# SensorThing_v1_0.net
KiCad netlist of a schematic drawn in Altium Designer
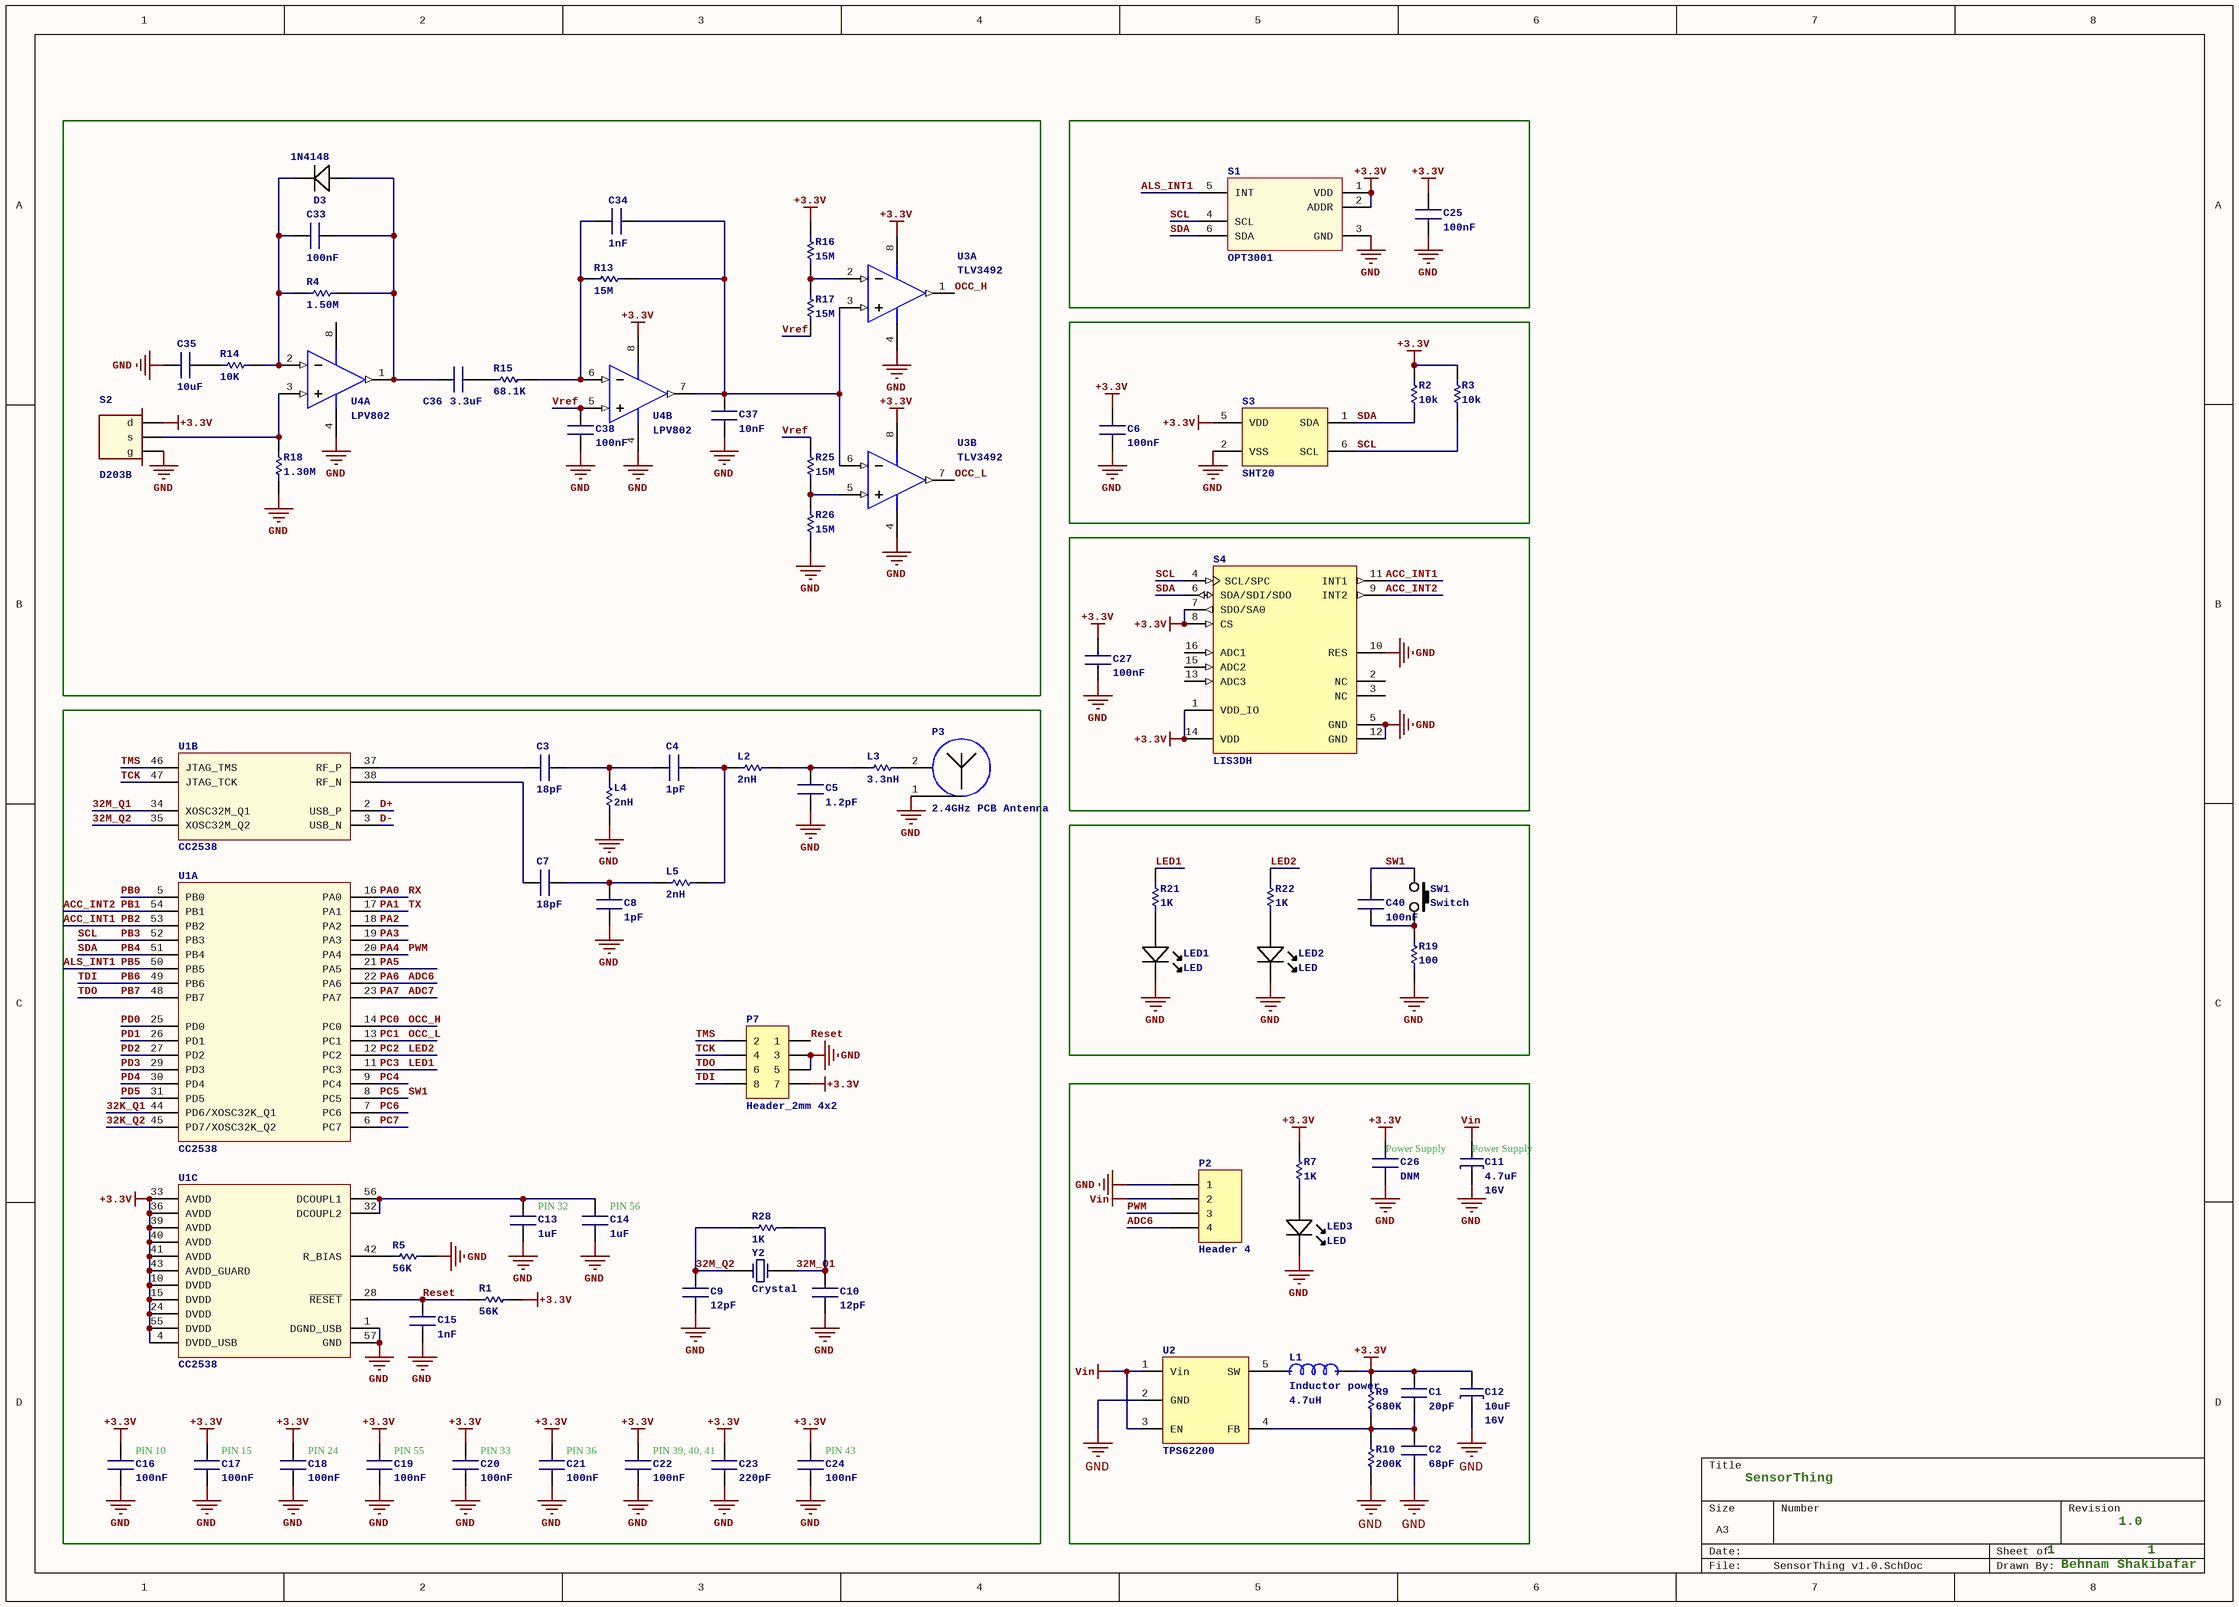
[diagram p0: SensorThing v1.0.SchDoc]

(export (version "E")
  (design (tool "Eeschema 10.0.6"))
  (components
    (comp (ref "C1")
      (value "Cap")
      (footprint "CAP 0603")
      (fields (field (name "VOLTAGE") "100V") (field (name "CAPACITY") "20pF"))
      (libsource (lib "Common") (part "Cap"))
    )
    (comp (ref "C2")
      (value "Cap")
      (footprint "CAP 0603")
      (fields (field (name "VOLTAGE") "100V") (field (name "CAPACITY") "68pF"))
      (libsource (lib "Common") (part "Cap"))
    )
    (comp (ref "C3")
      (value "Cap")
      (footprint "CAP 0603")
      (fields (field (name "VOLTAGE") "100V") (field (name "CAPACITY") "18pF"))
      (libsource (lib "Common") (part "Cap"))
    )
    (comp (ref "C4")
      (value "Cap")
      (footprint "CAP 0603")
      (fields (field (name "VOLTAGE") "100V") (field (name "CAPACITY") "1pF"))
      (libsource (lib "Common") (part "Cap"))
    )
    (comp (ref "C5")
      (value "Cap")
      (footprint "CAP 0603")
      (fields (field (name "VOLTAGE") "100V") (field (name "CAPACITY") "1.2pF"))
      (libsource (lib "Common") (part "Cap"))
    )
    (comp (ref "C6")
      (value "Cap")
      (footprint "CAP 0603")
      (fields (field (name "VOLTAGE") "100V") (field (name "CAPACITY") "100nF"))
      (libsource (lib "Common") (part "Cap"))
    )
    (comp (ref "C7")
      (value "Cap")
      (footprint "CAP 0603")
      (fields (field (name "VOLTAGE") "100V") (field (name "CAPACITY") "18pF"))
      (libsource (lib "Common") (part "Cap"))
    )
    (comp (ref "C8")
      (value "Cap")
      (footprint "CAP 0603")
      (fields (field (name "VOLTAGE") "100V") (field (name "CAPACITY") "1pF"))
      (libsource (lib "Common") (part "Cap"))
    )
    (comp (ref "C9")
      (value "Cap")
      (footprint "CAP 0603")
      (fields (field (name "VOLTAGE") "100V") (field (name "CAPACITY") "12pF"))
      (libsource (lib "Common") (part "Cap"))
    )
    (comp (ref "C10")
      (value "Cap")
      (footprint "CAP 0603")
      (fields (field (name "VOLTAGE") "100V") (field (name "CAPACITY") "12pF"))
      (libsource (lib "Common") (part "Cap"))
    )
    (comp (ref "C11")
      (value "Cap pol")
      (footprint "CAP A")
      (fields (field (name "CAPACITY") "4.7uF") (field (name "VOLTAGE") "16V"))
      (libsource (lib "Common") (part "Cap pol"))
    )
    (comp (ref "C12")
      (value "Cap pol")
      (footprint "CAP A")
      (fields (field (name "CAPACITY") "10uF") (field (name "VOLTAGE") "16V"))
      (libsource (lib "Common") (part "Cap pol"))
    )
    (comp (ref "C13")
      (value "Cap")
      (footprint "CAP 0603")
      (fields (field (name "VOLTAGE") "100V") (field (name "CAPACITY") "1uF"))
      (libsource (lib "Common") (part "Cap"))
    )
    (comp (ref "C14")
      (value "Cap")
      (footprint "CAP 0603")
      (fields (field (name "VOLTAGE") "100V") (field (name "CAPACITY") "1uF"))
      (libsource (lib "Common") (part "Cap"))
    )
    (comp (ref "C15")
      (value "Cap")
      (footprint "CAP 0603")
      (fields (field (name "VOLTAGE") "100V") (field (name "CAPACITY") "1nF"))
      (libsource (lib "Common") (part "Cap"))
    )
    (comp (ref "C16")
      (value "Cap")
      (footprint "CAP 0603")
      (fields (field (name "VOLTAGE") "100V") (field (name "CAPACITY") "100nF"))
      (libsource (lib "Common") (part "Cap"))
    )
    (comp (ref "C17")
      (value "Cap")
      (footprint "CAP 0603")
      (fields (field (name "VOLTAGE") "100V") (field (name "CAPACITY") "100nF"))
      (libsource (lib "Common") (part "Cap"))
    )
    (comp (ref "C18")
      (value "Cap")
      (footprint "CAP 0603")
      (fields (field (name "VOLTAGE") "100V") (field (name "CAPACITY") "100nF"))
      (libsource (lib "Common") (part "Cap"))
    )
    (comp (ref "C19")
      (value "Cap")
      (footprint "CAP 0603")
      (fields (field (name "VOLTAGE") "100V") (field (name "CAPACITY") "100nF"))
      (libsource (lib "Common") (part "Cap"))
    )
    (comp (ref "C20")
      (value "Cap")
      (footprint "CAP 0603")
      (fields (field (name "VOLTAGE") "100V") (field (name "CAPACITY") "100nF"))
      (libsource (lib "Common") (part "Cap"))
    )
    (comp (ref "C21")
      (value "Cap")
      (footprint "CAP 0603")
      (fields (field (name "VOLTAGE") "100V") (field (name "CAPACITY") "100nF"))
      (libsource (lib "Common") (part "Cap"))
    )
    (comp (ref "C22")
      (value "Cap")
      (footprint "CAP 0603")
      (fields (field (name "VOLTAGE") "100V") (field (name "CAPACITY") "100nF"))
      (libsource (lib "Common") (part "Cap"))
    )
    (comp (ref "C23")
      (value "Cap")
      (footprint "CAP 0603")
      (fields (field (name "VOLTAGE") "100V") (field (name "CAPACITY") "220pF"))
      (libsource (lib "Common") (part "Cap"))
    )
    (comp (ref "C24")
      (value "Cap")
      (footprint "CAP 0603")
      (fields (field (name "VOLTAGE") "100V") (field (name "CAPACITY") "100nF"))
      (libsource (lib "Common") (part "Cap"))
    )
    (comp (ref "C25")
      (value "Cap")
      (footprint "CAP 0603")
      (fields (field (name "VOLTAGE") "100V") (field (name "CAPACITY") "100nF"))
      (libsource (lib "Common") (part "Cap"))
    )
    (comp (ref "C26")
      (value "Cap")
      (footprint "CAP 0603")
      (fields (field (name "VOLTAGE") "100V") (field (name "CAPACITY") "DNM"))
      (libsource (lib "Common") (part "Cap"))
    )
    (comp (ref "C27")
      (value "Cap")
      (footprint "CAP 0603")
      (fields (field (name "VOLTAGE") "100V") (field (name "CAPACITY") "100nF"))
      (libsource (lib "Common") (part "Cap"))
    )
    (comp (ref "C33")
      (value "Cap")
      (footprint "CAP 0603")
      (fields (field (name "VOLTAGE") "100V") (field (name "CAPACITY") "100nF"))
      (libsource (lib "Common") (part "Cap"))
    )
    (comp (ref "C34")
      (value "Cap")
      (footprint "CAP 0603")
      (fields (field (name "VOLTAGE") "100V") (field (name "CAPACITY") "1nF"))
      (libsource (lib "Common") (part "Cap"))
    )
    (comp (ref "C35")
      (value "Cap")
      (footprint "CAP 0603")
      (fields (field (name "VOLTAGE") "100V") (field (name "CAPACITY") "10uF"))
      (libsource (lib "Common") (part "Cap"))
    )
    (comp (ref "C36")
      (value "Cap")
      (footprint "CAP 0603")
      (fields (field (name "VOLTAGE") "100V") (field (name "CAPACITY") "3.3uF"))
      (libsource (lib "Common") (part "Cap"))
    )
    (comp (ref "C37")
      (value "Cap")
      (footprint "CAP 0603")
      (fields (field (name "VOLTAGE") "100V") (field (name "CAPACITY") "10nF"))
      (libsource (lib "Common") (part "Cap"))
    )
    (comp (ref "C38")
      (value "Cap")
      (footprint "CAP 0603")
      (fields (field (name "VOLTAGE") "100V") (field (name "CAPACITY") "100nF"))
      (libsource (lib "Common") (part "Cap"))
    )
    (comp (ref "C40")
      (value "Cap")
      (footprint "CAP 0603")
      (fields (field (name "VOLTAGE") "100V") (field (name "CAPACITY") "100nF"))
      (libsource (lib "Common") (part "Cap"))
    )
    (comp (ref "D3") (value "1N4148") (footprint "SOD-523") (libsource (lib "Common") (part "Diode")))
    (comp (ref "L1")
      (value "Inductor power")
      (footprint "INDUCTOR 2520")
      (fields (field (name "ALTIUM_VALUE") "4.7uH"))
      (libsource (lib "Common") (part "Inductor power"))
    )
    (comp (ref "L2")
      (value "Res")
      (footprint "RES 0603")
      (description "Resistor")
      (fields (field (name "OHM") "2nH"))
      (libsource (lib "Common") (part "Res"))
    )
    (comp (ref "L3")
      (value "Res")
      (footprint "RES 0603")
      (description "Resistor")
      (fields (field (name "OHM") "3.3nH"))
      (libsource (lib "Common") (part "Res"))
    )
    (comp (ref "L4")
      (value "Res")
      (footprint "RES 0603")
      (description "Resistor")
      (fields (field (name "OHM") "2nH"))
      (libsource (lib "Common") (part "Res"))
    )
    (comp (ref "L5")
      (value "Res")
      (footprint "RES 0603")
      (description "Resistor")
      (fields (field (name "OHM") "2nH"))
      (libsource (lib "Common") (part "Res"))
    )
    (comp (ref "LED1")
      (value "LED")
      (footprint "LED 0603")
      (description "LED SMD")
      (libsource (lib "Common") (part "LED SMD"))
    )
    (comp (ref "LED2")
      (value "LED")
      (footprint "LED 0603")
      (description "LED SMD")
      (libsource (lib "Common") (part "LED SMD"))
    )
    (comp (ref "LED3")
      (value "LED")
      (footprint "LED 0603")
      (description "LED SMD")
      (libsource (lib "Common") (part "LED SMD"))
    )
    (comp (ref "P2")
      (value "Header 4")
      (footprint "HDR1X4")
      (description "Header, 4-Pin")
      (fields (field (name "PUBLISHER") "Altium Limited"))
      (libsource (lib "Miscellaneous Connectors") (part "Header 4"))
    )
    (comp (ref "P3")
      (value "2.4GHz PCB Antenna")
      (footprint "2.4 GHz Inverted F Antenna 1")
      (libsource (lib "My Lib") (part "2.4GHz PCB Antenna"))
    )
    (comp (ref "P7")
      (value "Header_2mm 4x2")
      (footprint "Header_2mm 4x2")
      (libsource (lib "Common") (part "Header_2mm 4x2"))
    )
    (comp (ref "R1")
      (value "Res")
      (footprint "RES 0603")
      (description "Resistor")
      (fields (field (name "OHM") "56K"))
      (libsource (lib "Common") (part "Res"))
    )
    (comp (ref "R2")
      (value "Res")
      (footprint "RES 0603")
      (description "Resistor")
      (fields (field (name "OHM") "10k"))
      (libsource (lib "Common") (part "Res"))
    )
    (comp (ref "R3")
      (value "Res")
      (footprint "RES 0603")
      (description "Resistor")
      (fields (field (name "OHM") "10k"))
      (libsource (lib "Common") (part "Res"))
    )
    (comp (ref "R4")
      (value "Res")
      (footprint "RES 0603")
      (description "Resistor")
      (fields (field (name "OHM") "1.50M"))
      (libsource (lib "Common") (part "Res"))
    )
    (comp (ref "R5")
      (value "Res")
      (footprint "RES 0603")
      (description "Resistor")
      (fields (field (name "OHM") "56K"))
      (libsource (lib "Common") (part "Res"))
    )
    (comp (ref "R7")
      (value "Res")
      (footprint "RES 0603")
      (description "Resistor")
      (fields (field (name "OHM") "1K"))
      (libsource (lib "Common") (part "Res"))
    )
    (comp (ref "R9")
      (value "Res")
      (footprint "RES 0603")
      (description "Resistor")
      (fields (field (name "OHM") "680K"))
      (libsource (lib "Common") (part "Res"))
    )
    (comp (ref "R10")
      (value "Res")
      (footprint "RES 0603")
      (description "Resistor")
      (fields (field (name "OHM") "200K"))
      (libsource (lib "Common") (part "Res"))
    )
    (comp (ref "R13")
      (value "Res")
      (footprint "RES 0603")
      (description "Resistor")
      (fields (field (name "OHM") "15M"))
      (libsource (lib "Common") (part "Res"))
    )
    (comp (ref "R14")
      (value "Res")
      (footprint "RES 0603")
      (description "Resistor")
      (fields (field (name "OHM") "10K"))
      (libsource (lib "Common") (part "Res"))
    )
    (comp (ref "R15")
      (value "Res")
      (footprint "RES 0603")
      (description "Resistor")
      (fields (field (name "OHM") "68.1K"))
      (libsource (lib "Common") (part "Res"))
    )
    (comp (ref "R16")
      (value "Res")
      (footprint "RES 0603")
      (description "Resistor")
      (fields (field (name "OHM") "15M"))
      (libsource (lib "Common") (part "Res"))
    )
    (comp (ref "R17")
      (value "Res")
      (footprint "RES 0603")
      (description "Resistor")
      (fields (field (name "OHM") "15M"))
      (libsource (lib "Common") (part "Res"))
    )
    (comp (ref "R18")
      (value "Res")
      (footprint "RES 0603")
      (description "Resistor")
      (fields (field (name "OHM") "1.30M"))
      (libsource (lib "Common") (part "Res"))
    )
    (comp (ref "R19")
      (value "Res")
      (footprint "RES 0603")
      (description "Resistor")
      (fields (field (name "OHM") "100"))
      (libsource (lib "Common") (part "Res"))
    )
    (comp (ref "R21")
      (value "Res")
      (footprint "RES 0603")
      (description "Resistor")
      (fields (field (name "OHM") "1K"))
      (libsource (lib "Common") (part "Res"))
    )
    (comp (ref "R22")
      (value "Res")
      (footprint "RES 0603")
      (description "Resistor")
      (fields (field (name "OHM") "1K"))
      (libsource (lib "Common") (part "Res"))
    )
    (comp (ref "R25")
      (value "Res")
      (footprint "RES 0603")
      (description "Resistor")
      (fields (field (name "OHM") "15M"))
      (libsource (lib "Common") (part "Res"))
    )
    (comp (ref "R26")
      (value "Res")
      (footprint "RES 0603")
      (description "Resistor")
      (fields (field (name "OHM") "15M"))
      (libsource (lib "Common") (part "Res"))
    )
    (comp (ref "R28")
      (value "Res")
      (footprint "RES 0603")
      (description "Resistor")
      (fields (field (name "OHM") "1K"))
      (libsource (lib "Common") (part "Res"))
    )
    (comp (ref "S1") (value "OPT3001") (footprint "USON-6pin") (libsource (lib "Chips") (part "OPT3001")))
    (comp (ref "S2") (value "D203B") (footprint "D203B") (libsource (lib "Common") (part "D203B PIR sensor")))
    (comp (ref "S3") (value "SHT20") (footprint "SHT20") (libsource (lib "My Lib") (part "SHT20")))
    (comp (ref "S4")
      (value "LIS3DH")
      (footprint "LGA16-3X3X1_N")
      (fields (field (name "MANUFACTURER") "STMicroelectronics"))
      (libsource (lib "STMicroelectronics Sensors & MEMS") (part "LIS3DH"))
    )
    (comp (ref "SW1")
      (value "Switch")
      (footprint "Switch Side-B3U")
      (description "micro Switch")
      (libsource (lib "Common") (part "Switch"))
    )
    (comp (ref "U1") (value "CC2538") (footprint "PVQFN56-CC2538") (libsource (lib "Chips") (part "CC2538")))
    (comp (ref "U2")
      (value "TPS62200")
      (footprint "SOT23-5")
      (description "NAND gate")
      (libsource (lib "My Lib") (part "TPS6220"))
    )
    (comp (ref "U3") (value "TLV3492") (footprint "VSSOP 8-Pin") (libsource (lib "My Lib") (part "TLV3492")))
    (comp (ref "U4") (value "LPV802") (footprint "VSSOP 8-Pin") (libsource (lib "My Lib") (part "LPV802")))
    (comp (ref "Y2") (value "Crystal") (footprint "Crystal 3225") (libsource (lib "Common") (part "Xtal")))
  )
  (nets
    (net (code "1") (name "+3.3V") (class "Default")
      (node (ref "C1") (pin "1") (pinfunction "1_1") (pintype "passive"))
      (node (ref "C12") (pin "1") (pinfunction "1_1") (pintype "passive"))
      (node (ref "C16") (pin "1") (pinfunction "1_1") (pintype "passive"))
      (node (ref "C17") (pin "1") (pinfunction "1_1") (pintype "passive"))
      (node (ref "C18") (pin "1") (pinfunction "1_1") (pintype "passive"))
      (node (ref "C19") (pin "1") (pinfunction "1_1") (pintype "passive"))
      (node (ref "C20") (pin "1") (pinfunction "1_1") (pintype "passive"))
      (node (ref "C21") (pin "1") (pinfunction "1_1") (pintype "passive"))
      (node (ref "C22") (pin "1") (pinfunction "1_1") (pintype "passive"))
      (node (ref "C23") (pin "1") (pinfunction "1_1") (pintype "passive"))
      (node (ref "C24") (pin "1") (pinfunction "1_1") (pintype "passive"))
      (node (ref "C25") (pin "1") (pinfunction "1_1") (pintype "passive"))
      (node (ref "C26") (pin "1") (pinfunction "1_1") (pintype "passive"))
      (node (ref "C27") (pin "1") (pinfunction "1_1") (pintype "passive"))
      (node (ref "C6") (pin "1") (pinfunction "1_1") (pintype "passive"))
      (node (ref "L1") (pin "2") (pinfunction "2_2") (pintype "passive"))
      (node (ref "P7") (pin "7") (pinfunction "7_7") (pintype "passive"))
      (node (ref "R1") (pin "2") (pinfunction "2_2") (pintype "passive"))
      (node (ref "R16") (pin "2") (pinfunction "2_2") (pintype "passive"))
      (node (ref "R2") (pin "1") (pinfunction "1_1") (pintype "passive"))
      (node (ref "R3") (pin "1") (pinfunction "1_1") (pintype "passive"))
      (node (ref "R7") (pin "1") (pinfunction "1_1") (pintype "passive"))
      (node (ref "R9") (pin "1") (pinfunction "1_1") (pintype "passive"))
      (node (ref "S1") (pin "1") (pinfunction "VDD_1") (pintype "power_in"))
      (node (ref "S1") (pin "2") (pinfunction "ADDR_2") (pintype "power_in"))
      (node (ref "S2") (pin "1") (pinfunction "d_1") (pintype "passive"))
      (node (ref "S3") (pin "5") (pinfunction "VDD_5") (pintype "passive"))
      (node (ref "S4") (pin "1") (pinfunction "VDD_IO_1") (pintype "power_in"))
      (node (ref "S4") (pin "14") (pinfunction "VDD_14") (pintype "power_in"))
      (node (ref "S4") (pin "7") (pinfunction "SDO/SA0_7") (pintype "output"))
      (node (ref "S4") (pin "8") (pinfunction "CS_8") (pintype "input"))
      (node (ref "U1") (pin "10") (pinfunction "DVDD_10") (pintype "power_in"))
      (node (ref "U1") (pin "15") (pinfunction "DVDD_15") (pintype "power_in"))
      (node (ref "U1") (pin "24") (pinfunction "DVDD_24") (pintype "power_in"))
      (node (ref "U1") (pin "33") (pinfunction "AVDD_33") (pintype "power_in"))
      (node (ref "U1") (pin "36") (pinfunction "AVDD_36") (pintype "power_in"))
      (node (ref "U1") (pin "39") (pinfunction "AVDD_39") (pintype "power_in"))
      (node (ref "U1") (pin "4") (pinfunction "DVDD_USB_4") (pintype "power_in"))
      (node (ref "U1") (pin "40") (pinfunction "AVDD_40") (pintype "power_in"))
      (node (ref "U1") (pin "41") (pinfunction "AVDD_41") (pintype "power_in"))
      (node (ref "U1") (pin "43") (pinfunction "AVDD_GUARD_43") (pintype "power_in"))
      (node (ref "U1") (pin "55") (pinfunction "DVDD_55") (pintype "power_in"))
      (node (ref "U3") (pin "8") (pinfunction "V+_8") (pintype "power_in"))
      (node (ref "U4") (pin "8") (pinfunction "V+_8") (pintype "power_in"))
    )
    (net (code "2") (name "/32K_Q1") (class "Default")
      (node (ref "U1") (pin "44") (pinfunction "PD6/XOSC32K_Q1_44") (pintype "power_in"))
    )
    (net (code "3") (name "/32K_Q2") (class "Default")
      (node (ref "U1") (pin "45") (pinfunction "PD7/XOSC32K_Q2_45") (pintype "power_in"))
    )
    (net (code "4") (name "/32M_Q1") (class "Default")
      (node (ref "C10") (pin "1") (pinfunction "1_1") (pintype "passive"))
      (node (ref "R28") (pin "2") (pinfunction "2_2") (pintype "passive"))
      (node (ref "U1") (pin "34") (pinfunction "XOSC32M_Q1_34") (pintype "passive"))
      (node (ref "Y2") (pin "2") (pinfunction "2_2") (pintype "passive"))
    )
    (net (code "5") (name "/32M_Q2") (class "Default")
      (node (ref "C9") (pin "1") (pinfunction "1_1") (pintype "passive"))
      (node (ref "R28") (pin "1") (pinfunction "1_1") (pintype "passive"))
      (node (ref "U1") (pin "35") (pinfunction "XOSC32M_Q2_35") (pintype "passive"))
      (node (ref "Y2") (pin "1") (pinfunction "1_1") (pintype "passive"))
    )
    (net (code "6") (name "/ACC_INT1") (class "Default")
      (node (ref "S4") (pin "11") (pinfunction "INT1_11") (pintype "output"))
      (node (ref "U1") (pin "53") (pinfunction "PB2_53") (pintype "power_in"))
    )
    (net (code "7") (name "/ACC_INT2") (class "Default")
      (node (ref "S4") (pin "9") (pinfunction "INT2_9") (pintype "output"))
      (node (ref "U1") (pin "54") (pinfunction "PB1_54") (pintype "power_in"))
    )
    (net (code "8") (name "/ADC6") (class "Default")
      (node (ref "P2") (pin "4") (pinfunction "4_4") (pintype "passive"))
      (node (ref "U1") (pin "22") (pinfunction "PA6_22") (pintype "power_in"))
    )
    (net (code "9") (name "/ADC7") (class "Default")
      (node (ref "U1") (pin "23") (pinfunction "PA7_23") (pintype "power_in"))
    )
    (net (code "10") (name "/ALS_INT1") (class "Default")
      (node (ref "S1") (pin "5") (pinfunction "INT_5") (pintype "power_in"))
      (node (ref "U1") (pin "50") (pinfunction "PB5_50") (pintype "power_in"))
    )
    (net (code "11") (name "/D+") (class "Default")
      (node (ref "U1") (pin "2") (pinfunction "USB_P_2") (pintype "passive"))
    )
    (net (code "12") (name "/D-") (class "Default")
      (node (ref "U1") (pin "3") (pinfunction "USB_N_3") (pintype "passive"))
    )
    (net (code "13") (name "/LED1") (class "Default")
      (node (ref "R21") (pin "1") (pinfunction "1_1") (pintype "passive"))
      (node (ref "U1") (pin "11") (pinfunction "PC3_11") (pintype "power_in"))
    )
    (net (code "14") (name "/LED2") (class "Default")
      (node (ref "R22") (pin "1") (pinfunction "1_1") (pintype "passive"))
      (node (ref "U1") (pin "12") (pinfunction "PC2_12") (pintype "power_in"))
    )
    (net (code "15") (name "/OCC_H") (class "Default")
      (node (ref "U1") (pin "14") (pinfunction "PC0_14") (pintype "power_in"))
      (node (ref "U3") (pin "1") (pinfunction "1_1") (pintype "output"))
    )
    (net (code "16") (name "/OCC_L") (class "Default")
      (node (ref "U1") (pin "13") (pinfunction "PC1_13") (pintype "power_in"))
      (node (ref "U3") (pin "7") (pinfunction "7_7") (pintype "output"))
    )
    (net (code "17") (name "/PA0") (class "Default")
      (node (ref "U1") (pin "16") (pinfunction "PA0_16") (pintype "power_in"))
    )
    (net (code "18") (name "/PA1") (class "Default")
      (node (ref "U1") (pin "17") (pinfunction "PA1_17") (pintype "power_in"))
    )
    (net (code "19") (name "/PA2") (class "Default")
      (node (ref "U1") (pin "18") (pinfunction "PA2_18") (pintype "power_in"))
    )
    (net (code "20") (name "/PA3") (class "Default")
      (node (ref "U1") (pin "19") (pinfunction "PA3_19") (pintype "power_in"))
    )
    (net (code "21") (name "/PA4") (class "Default")
      (node (ref "P2") (pin "3") (pinfunction "3_3") (pintype "passive"))
      (node (ref "U1") (pin "20") (pinfunction "PA4_20") (pintype "power_in"))
    )
    (net (code "22") (name "/PA5") (class "Default")
      (node (ref "U1") (pin "21") (pinfunction "PA5_21") (pintype "power_in"))
    )
    (net (code "23") (name "/PB0") (class "Default")
      (node (ref "U1") (pin "5") (pinfunction "PB0_5") (pintype "power_in"))
    )
    (net (code "24") (name "/PB3") (class "Default")
      (node (ref "R3") (pin "2") (pinfunction "2_2") (pintype "passive"))
      (node (ref "S1") (pin "4") (pinfunction "SCL_4") (pintype "power_in"))
      (node (ref "S3") (pin "6") (pinfunction "SCL_6") (pintype "passive"))
      (node (ref "S4") (pin "4") (pinfunction "SCL/SPC_4") (pintype "input"))
      (node (ref "U1") (pin "52") (pinfunction "PB3_52") (pintype "power_in"))
    )
    (net (code "25") (name "/PB4") (class "Default")
      (node (ref "R2") (pin "2") (pinfunction "2_2") (pintype "passive"))
      (node (ref "S1") (pin "6") (pinfunction "SDA_6") (pintype "power_in"))
      (node (ref "S3") (pin "1") (pinfunction "SDA_1") (pintype "passive"))
      (node (ref "S4") (pin "6") (pinfunction "SDA/SDI/SDO_6") (pintype "bidirectional"))
      (node (ref "U1") (pin "51") (pinfunction "PB4_51") (pintype "power_in"))
    )
    (net (code "26") (name "/PB6") (class "Default")
      (node (ref "P7") (pin "8") (pinfunction "8_8") (pintype "passive"))
      (node (ref "U1") (pin "49") (pinfunction "PB6_49") (pintype "power_in"))
    )
    (net (code "27") (name "/PB7") (class "Default")
      (node (ref "P7") (pin "6") (pinfunction "6_6") (pintype "passive"))
      (node (ref "U1") (pin "48") (pinfunction "PB7_48") (pintype "power_in"))
    )
    (net (code "28") (name "/PC4") (class "Default")
      (node (ref "U1") (pin "9") (pinfunction "PC4_9") (pintype "power_in"))
    )
    (net (code "29") (name "/PC5") (class "Default")
      (node (ref "C40") (pin "1") (pinfunction "1_1") (pintype "passive"))
      (node (ref "SW1") (pin "1") (pintype "passive"))
      (node (ref "U1") (pin "8") (pinfunction "PC5_8") (pintype "power_in"))
    )
    (net (code "30") (name "/PC6") (class "Default")
      (node (ref "U1") (pin "7") (pinfunction "PC6_7") (pintype "power_in"))
    )
    (net (code "31") (name "/PC7") (class "Default")
      (node (ref "U1") (pin "6") (pinfunction "PC7_6") (pintype "power_in"))
    )
    (net (code "32") (name "/PD0") (class "Default")
      (node (ref "U1") (pin "25") (pinfunction "PD0_25") (pintype "power_in"))
    )
    (net (code "33") (name "/PD1") (class "Default")
      (node (ref "U1") (pin "26") (pinfunction "PD1_26") (pintype "power_in"))
    )
    (net (code "34") (name "/PD2") (class "Default")
      (node (ref "U1") (pin "27") (pinfunction "PD2_27") (pintype "power_in"))
    )
    (net (code "35") (name "/PD3") (class "Default")
      (node (ref "U1") (pin "29") (pinfunction "PD3_29") (pintype "power_in"))
    )
    (net (code "36") (name "/PD4") (class "Default")
      (node (ref "U1") (pin "30") (pinfunction "PD4_30") (pintype "power_in"))
    )
    (net (code "37") (name "/PD5") (class "Default")
      (node (ref "U1") (pin "31") (pinfunction "PD5_31") (pintype "power_in"))
    )
    (net (code "38") (name "/Reset") (class "Default")
      (node (ref "C15") (pin "1") (pinfunction "1_1") (pintype "passive"))
      (node (ref "P7") (pin "1") (pinfunction "1_1") (pintype "passive"))
      (node (ref "R1") (pin "1") (pinfunction "1_1") (pintype "passive"))
      (node (ref "U1") (pin "28") (pinfunction "~{RESET}_28") (pintype "power_in"))
    )
    (net (code "39") (name "/TCK") (class "Default")
      (node (ref "P7") (pin "4") (pinfunction "4_4") (pintype "passive"))
      (node (ref "U1") (pin "47") (pinfunction "JTAG_TCK_47") (pintype "power_in"))
    )
    (net (code "40") (name "/TMS") (class "Default")
      (node (ref "P7") (pin "2") (pinfunction "2_2") (pintype "passive"))
      (node (ref "U1") (pin "46") (pinfunction "JTAG_TMS_46") (pintype "power_in"))
    )
    (net (code "41") (name "/Vref") (class "Default")
      (node (ref "C38") (pin "1") (pinfunction "1_1") (pintype "passive"))
      (node (ref "R17") (pin "1") (pinfunction "1_1") (pintype "passive"))
      (node (ref "R25") (pin "2") (pinfunction "2_2") (pintype "passive"))
      (node (ref "U4") (pin "5") (pinfunction "5_5") (pintype "input"))
    )
    (net (code "42") (name "GND") (class "Default")
      (node (ref "C10") (pin "2") (pinfunction "2_2") (pintype "passive"))
      (node (ref "C11") (pin "2") (pinfunction "2_2") (pintype "passive"))
      (node (ref "C12") (pin "2") (pinfunction "2_2") (pintype "passive"))
      (node (ref "C13") (pin "2") (pinfunction "2_2") (pintype "passive"))
      (node (ref "C14") (pin "2") (pinfunction "2_2") (pintype "passive"))
      (node (ref "C15") (pin "2") (pinfunction "2_2") (pintype "passive"))
      (node (ref "C16") (pin "2") (pinfunction "2_2") (pintype "passive"))
      (node (ref "C17") (pin "2") (pinfunction "2_2") (pintype "passive"))
      (node (ref "C18") (pin "2") (pinfunction "2_2") (pintype "passive"))
      (node (ref "C19") (pin "2") (pinfunction "2_2") (pintype "passive"))
      (node (ref "C2") (pin "2") (pinfunction "2_2") (pintype "passive"))
      (node (ref "C20") (pin "2") (pinfunction "2_2") (pintype "passive"))
      (node (ref "C21") (pin "2") (pinfunction "2_2") (pintype "passive"))
      (node (ref "C22") (pin "2") (pinfunction "2_2") (pintype "passive"))
      (node (ref "C23") (pin "2") (pinfunction "2_2") (pintype "passive"))
      (node (ref "C24") (pin "2") (pinfunction "2_2") (pintype "passive"))
      (node (ref "C25") (pin "2") (pinfunction "2_2") (pintype "passive"))
      (node (ref "C26") (pin "2") (pinfunction "2_2") (pintype "passive"))
      (node (ref "C27") (pin "2") (pinfunction "2_2") (pintype "passive"))
      (node (ref "C35") (pin "2") (pinfunction "2_2") (pintype "passive"))
      (node (ref "C37") (pin "2") (pinfunction "2_2") (pintype "passive"))
      (node (ref "C38") (pin "2") (pinfunction "2_2") (pintype "passive"))
      (node (ref "C5") (pin "2") (pinfunction "2_2") (pintype "passive"))
      (node (ref "C6") (pin "2") (pinfunction "2_2") (pintype "passive"))
      (node (ref "C8") (pin "2") (pinfunction "2_2") (pintype "passive"))
      (node (ref "C9") (pin "2") (pinfunction "2_2") (pintype "passive"))
      (node (ref "L4") (pin "1") (pinfunction "1_1") (pintype "passive"))
      (node (ref "LED1") (pin "2") (pinfunction "2_2") (pintype "passive"))
      (node (ref "LED2") (pin "2") (pinfunction "2_2") (pintype "passive"))
      (node (ref "LED3") (pin "2") (pinfunction "2_2") (pintype "passive"))
      (node (ref "P2") (pin "1") (pinfunction "1_1") (pintype "passive"))
      (node (ref "P3") (pin "1") (pintype "passive"))
      (node (ref "P7") (pin "3") (pinfunction "3_3") (pintype "passive"))
      (node (ref "P7") (pin "5") (pinfunction "5_5") (pintype "passive"))
      (node (ref "R10") (pin "2") (pinfunction "2_2") (pintype "passive"))
      (node (ref "R18") (pin "1") (pinfunction "1_1") (pintype "passive"))
      (node (ref "R19") (pin "2") (pinfunction "2_2") (pintype "passive"))
      (node (ref "R26") (pin "1") (pinfunction "1_1") (pintype "passive"))
      (node (ref "R5") (pin "2") (pinfunction "2_2") (pintype "passive"))
      (node (ref "S1") (pin "3") (pinfunction "GND_3") (pintype "power_in"))
      (node (ref "S2") (pin "3") (pinfunction "g_3") (pintype "passive"))
      (node (ref "S3") (pin "2") (pinfunction "VSS_2") (pintype "passive"))
      (node (ref "S4") (pin "10") (pinfunction "RES_10") (pintype "passive"))
      (node (ref "S4") (pin "12") (pinfunction "GND_12") (pintype "power_in"))
      (node (ref "S4") (pin "5") (pinfunction "GND_5") (pintype "power_in"))
      (node (ref "U1") (pin "1") (pinfunction "DGND_USB_1") (pintype "power_in"))
      (node (ref "U1") (pin "57") (pinfunction "GND_57") (pintype "power_in"))
      (node (ref "U2") (pin "2") (pinfunction "GND_2") (pintype "passive"))
      (node (ref "U3") (pin "4") (pinfunction "4_4") (pintype "power_in"))
      (node (ref "U4") (pin "4") (pinfunction "4_4") (pintype "power_in"))
    )
    (net (code "43") (name "Net-(C3-Pad1)") (class "Default")
      (node (ref "C3") (pin "1") (pinfunction "1_1") (pintype "passive"))
      (node (ref "C4") (pin "2") (pinfunction "2_2") (pintype "passive"))
      (node (ref "L4") (pin "2") (pinfunction "2_2") (pintype "passive"))
    )
    (net (code "44") (name "Net-(C4-Pad1)") (class "Default")
      (node (ref "C4") (pin "1") (pinfunction "1_1") (pintype "passive"))
      (node (ref "L2") (pin "2") (pinfunction "2_2") (pintype "passive"))
      (node (ref "L5") (pin "1") (pinfunction "1_1") (pintype "passive"))
    )
    (net (code "45") (name "Net-(C5-Pad1)") (class "Default")
      (node (ref "C5") (pin "1") (pinfunction "1_1") (pintype "passive"))
      (node (ref "L2") (pin "1") (pinfunction "1_1") (pintype "passive"))
      (node (ref "L3") (pin "2") (pinfunction "2_2") (pintype "passive"))
    )
    (net (code "46") (name "Net-(C7-Pad1)") (class "Default")
      (node (ref "C7") (pin "1") (pinfunction "1_1") (pintype "passive"))
      (node (ref "C8") (pin "1") (pinfunction "1_1") (pintype "passive"))
      (node (ref "L5") (pin "2") (pinfunction "2_2") (pintype "passive"))
    )
    (net (code "47") (name "Net-(C33-Pad1)") (class "Default")
      (node (ref "C33") (pin "1") (pinfunction "1_1") (pintype "passive"))
      (node (ref "D3") (pin "2") (pinfunction "2_2") (pintype "passive"))
      (node (ref "R14") (pin "2") (pinfunction "2_2") (pintype "passive"))
      (node (ref "R4") (pin "1") (pinfunction "1_1") (pintype "passive"))
      (node (ref "U4") (pin "2") (pinfunction "2_2") (pintype "input"))
    )
    (net (code "48") (name "Net-(C33-Pad2)") (class "Default")
      (node (ref "C33") (pin "2") (pinfunction "2_2") (pintype "passive"))
      (node (ref "C36") (pin "2") (pinfunction "2_2") (pintype "passive"))
      (node (ref "D3") (pin "1") (pinfunction "1_1") (pintype "passive"))
      (node (ref "R4") (pin "2") (pinfunction "2_2") (pintype "passive"))
      (node (ref "U4") (pin "1") (pinfunction "1_1") (pintype "output"))
    )
    (net (code "49") (name "Net-(C34-Pad1)") (class "Default")
      (node (ref "C34") (pin "1") (pinfunction "1_1") (pintype "passive"))
      (node (ref "R13") (pin "1") (pinfunction "1_1") (pintype "passive"))
      (node (ref "R15") (pin "2") (pinfunction "2_2") (pintype "passive"))
      (node (ref "U4") (pin "6") (pinfunction "6_6") (pintype "input"))
    )
    (net (code "50") (name "Net-(C34-Pad2)") (class "Default")
      (node (ref "C34") (pin "2") (pinfunction "2_2") (pintype "passive"))
      (node (ref "C37") (pin "1") (pinfunction "1_1") (pintype "passive"))
      (node (ref "R13") (pin "2") (pinfunction "2_2") (pintype "passive"))
      (node (ref "U3") (pin "3") (pinfunction "3_3") (pintype "input"))
      (node (ref "U3") (pin "6") (pinfunction "6_6") (pintype "input"))
      (node (ref "U4") (pin "7") (pinfunction "7_7") (pintype "output"))
    )
    (net (code "51") (name "Net-(C35-Pad1)") (class "Default")
      (node (ref "C35") (pin "1") (pinfunction "1_1") (pintype "passive"))
      (node (ref "R14") (pin "1") (pinfunction "1_1") (pintype "passive"))
    )
    (net (code "52") (name "Net-(C36-Pad1)") (class "Default")
      (node (ref "C36") (pin "1") (pinfunction "1_1") (pintype "passive"))
      (node (ref "R15") (pin "1") (pinfunction "1_1") (pintype "passive"))
    )
    (net (code "53") (name "Net-(C40-Pad2)") (class "Default")
      (node (ref "C40") (pin "2") (pinfunction "2_2") (pintype "passive"))
      (node (ref "R19") (pin "1") (pinfunction "1_1") (pintype "passive"))
      (node (ref "SW1") (pin "2") (pintype "passive"))
    )
    (net (code "54") (name "Net-(L3-Pad1)") (class "Default")
      (node (ref "L3") (pin "1") (pinfunction "1_1") (pintype "passive"))
      (node (ref "P3") (pin "2") (pintype "passive"))
    )
    (net (code "55") (name "Net-(LED1-Pad1)") (class "Default")
      (node (ref "LED1") (pin "1") (pinfunction "1_1") (pintype "passive"))
      (node (ref "R21") (pin "2") (pinfunction "2_2") (pintype "passive"))
    )
    (net (code "56") (name "Net-(LED2-Pad1)") (class "Default")
      (node (ref "LED2") (pin "1") (pinfunction "1_1") (pintype "passive"))
      (node (ref "R22") (pin "2") (pinfunction "2_2") (pintype "passive"))
    )
    (net (code "57") (name "Net-(LED3-Pad1)") (class "Default")
      (node (ref "LED3") (pin "1") (pinfunction "1_1") (pintype "passive"))
      (node (ref "R7") (pin "2") (pinfunction "2_2") (pintype "passive"))
    )
    (net (code "58") (name "Net-(R16-Pad1)") (class "Default")
      (node (ref "R16") (pin "1") (pinfunction "1_1") (pintype "passive"))
      (node (ref "R17") (pin "2") (pinfunction "2_2") (pintype "passive"))
      (node (ref "U3") (pin "2") (pinfunction "2_2") (pintype "input"))
    )
    (net (code "59") (name "Net-(R25-Pad1)") (class "Default")
      (node (ref "R25") (pin "1") (pinfunction "1_1") (pintype "passive"))
      (node (ref "R26") (pin "2") (pinfunction "2_2") (pintype "passive"))
      (node (ref "U3") (pin "5") (pinfunction "5_5") (pintype "input"))
    )
    (net (code "60") (name "Net-(S2-s)") (class "Default")
      (node (ref "R18") (pin "2") (pinfunction "2_2") (pintype "passive"))
      (node (ref "S2") (pin "2") (pinfunction "s_2") (pintype "passive"))
      (node (ref "U4") (pin "3") (pinfunction "3_3") (pintype "input"))
    )
    (net (code "61") (name "Net-(U1B-RF_N)") (class "Default")
      (node (ref "C7") (pin "2") (pinfunction "2_2") (pintype "passive"))
      (node (ref "U1") (pin "38") (pinfunction "RF_N_38") (pintype "passive"))
    )
    (net (code "62") (name "Net-(U1B-RF_P)") (class "Default")
      (node (ref "C3") (pin "2") (pinfunction "2_2") (pintype "passive"))
      (node (ref "U1") (pin "37") (pinfunction "RF_P_37") (pintype "passive"))
    )
    (net (code "63") (name "Net-(U1C-DCOUPL1)") (class "Default")
      (node (ref "C13") (pin "1") (pinfunction "1_1") (pintype "passive"))
      (node (ref "C14") (pin "1") (pinfunction "1_1") (pintype "passive"))
      (node (ref "U1") (pin "32") (pinfunction "DCOUPL2_32") (pintype "power_in"))
      (node (ref "U1") (pin "56") (pinfunction "DCOUPL1_56") (pintype "power_in"))
    )
    (net (code "64") (name "Net-(U1C-R_BIAS)") (class "Default")
      (node (ref "R5") (pin "1") (pinfunction "1_1") (pintype "passive"))
      (node (ref "U1") (pin "42") (pinfunction "R_BIAS_42") (pintype "passive"))
    )
    (net (code "65") (name "Net-(U2-FB)") (class "Default")
      (node (ref "C1") (pin "2") (pinfunction "2_2") (pintype "passive"))
      (node (ref "C2") (pin "1") (pinfunction "1_1") (pintype "passive"))
      (node (ref "R10") (pin "1") (pinfunction "1_1") (pintype "passive"))
      (node (ref "R9") (pin "2") (pinfunction "2_2") (pintype "passive"))
      (node (ref "U2") (pin "4") (pinfunction "FB_4") (pintype "passive"))
    )
    (net (code "66") (name "Net-(U2-SW)") (class "Default")
      (node (ref "L1") (pin "1") (pinfunction "1_1") (pintype "passive"))
      (node (ref "U2") (pin "5") (pinfunction "SW_5") (pintype "passive"))
    )
    (net (code "67") (name "Vin") (class "Default")
      (node (ref "C11") (pin "1") (pinfunction "1_1") (pintype "passive"))
      (node (ref "P2") (pin "2") (pinfunction "2_2") (pintype "passive"))
      (node (ref "U2") (pin "1") (pinfunction "Vin_1") (pintype "passive"))
      (node (ref "U2") (pin "3") (pinfunction "EN_3") (pintype "passive"))
    )
    (net (code "68") (name "unconnected-(S4-ADC1-Pad16)") (class "Default")
      (node (ref "S4") (pin "16") (pinfunction "ADC1_16") (pintype "input"))
    )
    (net (code "69") (name "unconnected-(S4-ADC2-Pad15)") (class "Default")
      (node (ref "S4") (pin "15") (pinfunction "ADC2_15") (pintype "input"))
    )
    (net (code "70") (name "unconnected-(S4-ADC3-Pad13)") (class "Default")
      (node (ref "S4") (pin "13") (pinfunction "ADC3_13") (pintype "input"))
    )
    (net (code "71") (name "unconnected-(S4-NC-Pad2)") (class "Default")
      (node (ref "S4") (pin "2") (pinfunction "NC_2") (pintype "passive"))
    )
    (net (code "72") (name "unconnected-(S4-NC-Pad3)") (class "Default")
      (node (ref "S4") (pin "3") (pinfunction "NC_3") (pintype "passive"))
    )
    (net (code "73") (name "unconnected-(U4A-V+-Pad8)") (class "Default")
      (node (ref "U4") (pin "8") (pinfunction "V+_8") (pintype "power_in"))
    )
  )
)
